# sequencer_final_version.net
KiCad netlist of a schematic drawn in Altium Designer
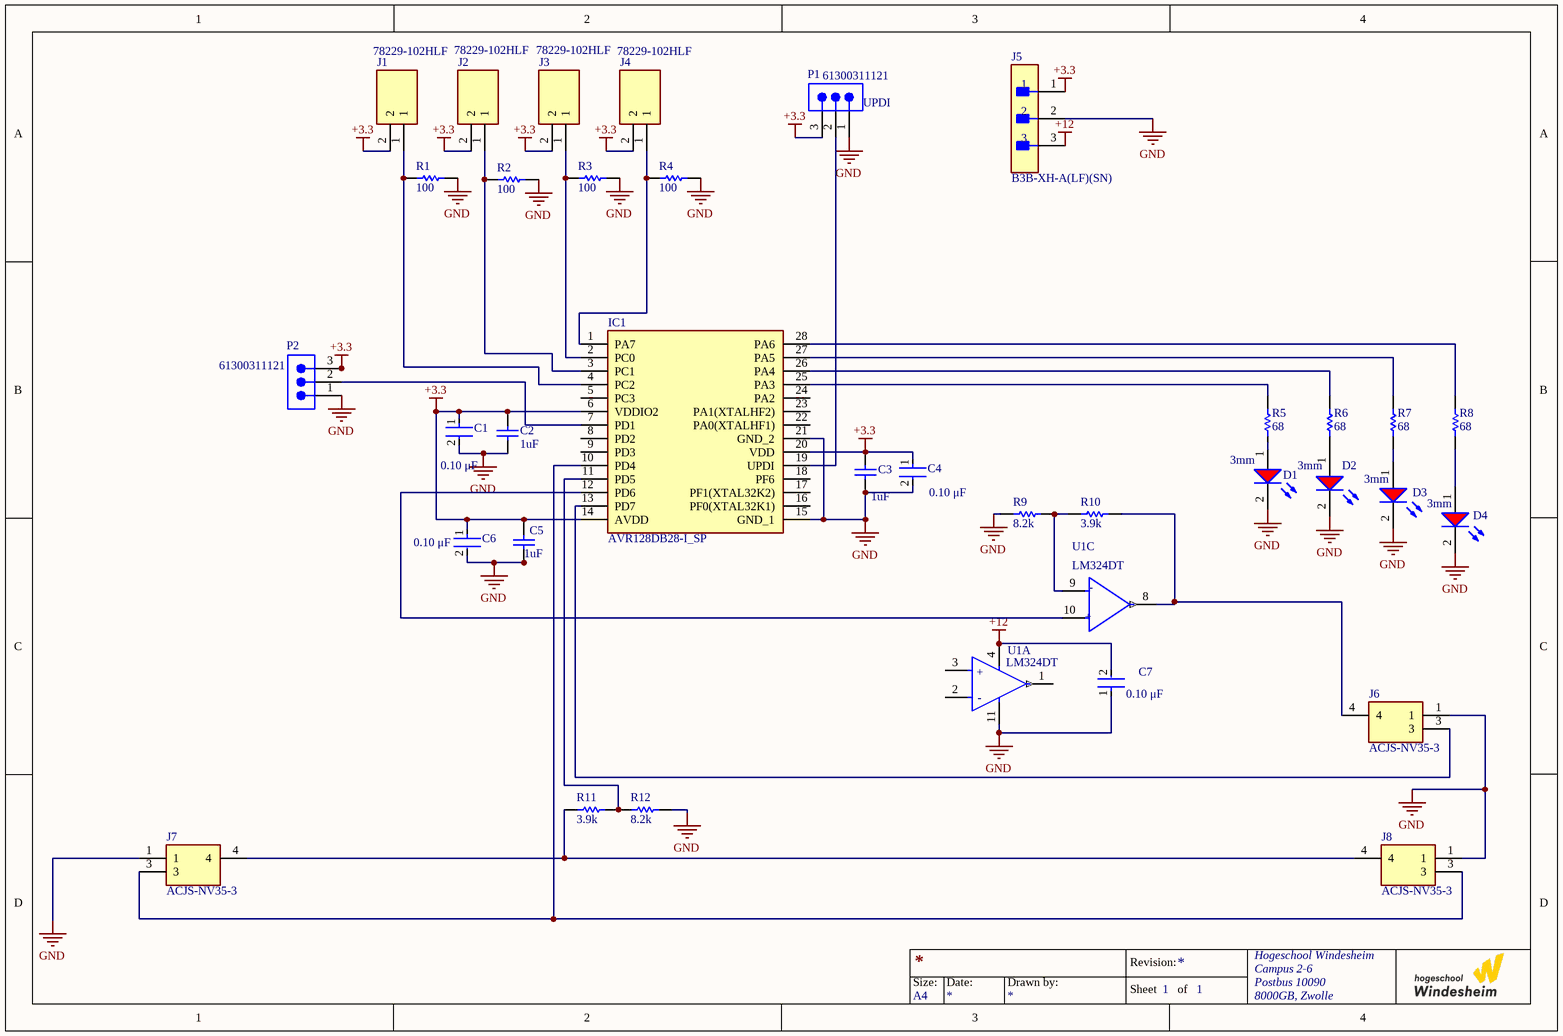
[diagram p0: sequencer final version.SchDoc]

(export (version "E")
  (design (tool "Eeschema 10.0.6"))
  (components
    (comp (ref "C1")
      (value "C1206C104K2RACTU")
      (footprint "FP-C1206C-EB-MFG")
      (description "CAP CER 0.1UF 200V 10% X7R 1206")
      (fields
        (field (name "TOLERANCE") "0.1")
        (field (name "OCTOPART") "https://octopart.com/c1206c104k2ractu-kemet-9138344")
        (field (name "CAPACITANCE") "0.10 μF")
      )
      (libsource (lib "Altium Content Vault") (part "b4654b650e69147ec39a6b967a45e02"))
    )
    (comp (ref "C2")
      (value "C1206C105K5RACTU")
      (footprint "CAPC3216X110X50LL20T25")
      (description "Chip Capacitor, 1 uF, +/- 10%, 50 V, -55 to 125 degC, 1206 (3216 Metric), RoHS, Tape and Reel")
      (fields
        (field (name "CAPACITANCE") "1uF")
        (field (name "MANUFACTURER") "Kemet")
        (field (name "TOLERANCE") "10%")
      )
      (libsource (lib "Altium Content Vault") (part "CAP-NP-2"))
    )
    (comp (ref "C3")
      (value "C1206C105K5RACTU")
      (footprint "CAPC3216X110X50LL20T25")
      (description "Chip Capacitor, 1 uF, +/- 10%, 50 V, -55 to 125 degC, 1206 (3216 Metric), RoHS, Tape and Reel")
      (fields
        (field (name "CAPACITANCE") "1uF")
        (field (name "MANUFACTURER") "Kemet")
        (field (name "TOLERANCE") "10%")
      )
      (libsource (lib "Altium Content Vault") (part "CAP-NP-2"))
    )
    (comp (ref "C4")
      (value "0.10 μF")
      (footprint "FP-C1206C-EB-MFG")
      (description "CAP CER 0.1UF 200V 10% X7R 1206")
      (fields (field (name "TOLERANCE") "0.1") (field (name "MANUFACTURER PART NUMBER") "C1206C104K2RACTU"))
      (libsource (lib "Altium Content Vault") (part "b4654b650e69147ec39a6b967a45e02"))
    )
    (comp (ref "C5")
      (value "C1206C105K5RACTU")
      (footprint "CAPC3216X110X50LL20T25")
      (description "Chip Capacitor, 1 uF, +/- 10%, 50 V, -55 to 125 degC, 1206 (3216 Metric), RoHS, Tape and Reel")
      (fields
        (field (name "CAPACITANCE") "1uF")
        (field (name "MANUFACTURER") "Kemet")
        (field (name "TOLERANCE") "10%")
      )
      (libsource (lib "Altium Content Vault") (part "CAP-NP-2"))
    )
    (comp (ref "C6")
      (value "0.10 μF")
      (footprint "FP-C1206C-EB-MFG")
      (description "CAP CER 0.1UF 200V 10% X7R 1206")
      (fields (field (name "TOLERANCE") "0.1") (field (name "MANUFACTURER PART NUMBER") "C1206C104K2RACTU"))
      (libsource (lib "Altium Content Vault") (part "b4654b650e69147ec39a6b967a45e02"))
    )
    (comp (ref "C7")
      (value "0.10 μF")
      (footprint "FP-C1206C-EB-MFG")
      (description "CAP CER 0.1UF 200V 10% X7R 1206")
      (fields (field (name "TOLERANCE") "0.1") (field (name "MANUFACTURER PART NUMBER") "C1206C104K2RACTU"))
      (libsource (lib "Altium Content Vault") (part "b4654b650e69147ec39a6b967a45e02"))
    )
    (comp (ref "D1")
      (value "151031SS04000")
      (footprint "WL-TMRC_D3.95H5.3")
      (fields (field (name "LENS SIZE") "3mm"))
      (libsource (lib "Altium Content Vault") (part "LED_Red_1A-2K"))
    )
    (comp (ref "D2")
      (value "151031SS04000")
      (footprint "WL-TMRC_D3.95H5.3")
      (fields (field (name "LENS SIZE") "3mm"))
      (libsource (lib "Altium Content Vault") (part "LED_Red_1A-2K"))
    )
    (comp (ref "D3")
      (value "151031SS04000")
      (footprint "WL-TMRC_D3.95H5.3")
      (fields (field (name "LENS SIZE") "3mm"))
      (libsource (lib "Altium Content Vault") (part "LED_Red_1A-2K"))
    )
    (comp (ref "D4")
      (value "151031SS04000")
      (footprint "WL-TMRC_D3.95H5.3")
      (fields (field (name "LENS SIZE") "3mm"))
      (libsource (lib "Altium Content Vault") (part "LED_Red_1A-2K"))
    )
    (comp (ref "IC1")
      (value "AVR128DB28-I_SP")
      (footprint "SamacSys:DIP794W56P254L3486H508Q28N")
      (description "Integrated Circuit")
      (fields
        (field (name "MANUFACTURER_PART_NUMBER") "AVR128DB28-I/SP")
        (field (name "MOUSER PART NUMBER") "579-AVR128DB28-I/SP")
      )
      (libsource (lib "*") (part "AVR128DB28-I_SP"))
    )
    (comp (ref "J1")
      (value "78229-102HLF")
      (footprint "SamacSys:HDRV2W67P0X254_1X2_508X241X1082P")
      (description "Connector")
      (libsource (lib "*") (part "78229-102HLF"))
    )
    (comp (ref "J2")
      (value "78229-102HLF")
      (footprint "SamacSys:HDRV2W67P0X254_1X2_508X241X1082P")
      (description "Connector")
      (libsource (lib "*") (part "78229-102HLF"))
    )
    (comp (ref "J3")
      (value "78229-102HLF")
      (footprint "SamacSys:HDRV2W67P0X254_1X2_508X241X1082P")
      (description "Connector")
      (libsource (lib "*") (part "78229-102HLF"))
    )
    (comp (ref "J4")
      (value "78229-102HLF")
      (footprint "SamacSys:HDRV2W67P0X254_1X2_508X241X1082P")
      (description "Connector")
      (libsource (lib "*") (part "78229-102HLF"))
    )
    (comp (ref "J5")
      (value "B3B-XH-A(LF)(SN)")
      (footprint "FP-B3B-XH-A_LF_SN-MFG")
      (description "CONN HEADER VERT 3POS 2.5MM")
      (libsource (lib "Altium Content Vault") (part "0d3f023dd272f625e17a2be33dea85f"))
    )
    (comp (ref "J6")
      (value "ACJS-NV35-3")
      (footprint "SamacSys:ACJSNV353")
      (description "Connector")
      (fields (field (name "MOUSER PART NUMBER") "523-ACJS-NV35-3"))
      (libsource (lib "*") (part "ACJS-NV35-3"))
    )
    (comp (ref "J7")
      (value "ACJS-NV35-3")
      (footprint "SamacSys:ACJSNV353")
      (description "Connector")
      (fields (field (name "MOUSER PART NUMBER") "523-ACJS-NV35-3"))
      (libsource (lib "") (part "ACJS-NV35-3_1"))
    )
    (comp (ref "J8")
      (value "ACJS-NV35-3")
      (footprint "SamacSys:ACJSNV353")
      (description "Connector")
      (fields (field (name "MOUSER PART NUMBER") "523-ACJS-NV35-3"))
      (libsource (lib "*") (part "ACJS-NV35-3"))
    )
    (comp (ref "P1")
      (value "61300311121")
      (footprint "61300311121")
      (description "Potmeter connectie")
      (libsource (lib "Altium Content Vault") (part "Header_Male_1R_03P"))
    )
    (comp (ref "P2")
      (value "61300311121")
      (footprint "61300311121")
      (description "Potmeter connectie")
      (libsource (lib "Altium Content Vault") (part "Header_Male_1R_03P"))
    )
    (comp (ref "R1")
      (value "100")
      (footprint "RESC3216X70X50NL05T20")
      (fields (field (name "MANUFACTURER") "Panasonic") (field (name "PART NUMBER") "ERJ-8ENF1000V"))
      (libsource (lib "Altium Content Vault") (part "RES"))
    )
    (comp (ref "R2")
      (value "100")
      (footprint "RESC3216X70X50NL05T20")
      (fields (field (name "MANUFACTURER") "Panasonic") (field (name "PART NUMBER") "ERJ-8ENF1000V"))
      (libsource (lib "Altium Content Vault") (part "RES"))
    )
    (comp (ref "R3")
      (value "100")
      (footprint "RESC3216X70X50NL05T20")
      (fields (field (name "MANUFACTURER") "Panasonic") (field (name "PART NUMBER") "ERJ-8ENF1000V"))
      (libsource (lib "Altium Content Vault") (part "RES"))
    )
    (comp (ref "R4")
      (value "100")
      (footprint "RESC3216X70X50NL05T20")
      (fields (field (name "MANUFACTURER") "Panasonic") (field (name "PART NUMBER") "ERJ-8ENF1000V"))
      (libsource (lib "Altium Content Vault") (part "RES"))
    )
    (comp (ref "R5")
      (value "68")
      (footprint "RESC3216X60X45LL10T20")
      (fields (field (name "MANUFACTURER") "Vishay Dale") (field (name "PART NUMBER") "CRCW120668R0FKEA"))
      (libsource (lib "Altium Content Vault") (part "RES"))
    )
    (comp (ref "R6")
      (value "68")
      (footprint "RESC3216X60X45LL10T20")
      (fields (field (name "MANUFACTURER") "Vishay Dale") (field (name "PART NUMBER") "CRCW120668R0FKEA"))
      (libsource (lib "Altium Content Vault") (part "RES"))
    )
    (comp (ref "R7")
      (value "68")
      (footprint "RESC3216X60X45LL10T20")
      (fields (field (name "MANUFACTURER") "Vishay Dale") (field (name "PART NUMBER") "CRCW120668R0FKEA"))
      (libsource (lib "Altium Content Vault") (part "RES"))
    )
    (comp (ref "R8")
      (value "68")
      (footprint "RESC3216X60X45LL10T20")
      (fields (field (name "MANUFACTURER") "Vishay Dale") (field (name "PART NUMBER") "CRCW120668R0FKEA"))
      (libsource (lib "Altium Content Vault") (part "RES"))
    )
    (comp (ref "R9")
      (value "8.2k")
      (footprint "RESC3216X60X45NL10T20")
      (fields (field (name "MANUFACTURER") "Vishay Dale") (field (name "PART NUMBER") "CRCW12063K90FKEA"))
      (libsource (lib "Altium Content Vault") (part "RES"))
    )
    (comp (ref "R10")
      (value "3.9k")
      (footprint "RESC3216X70X50ML20T25")
      (fields (field (name "PART NUMBER") "ERA8AEB202V") (field (name "MANUFACTURER") "Panasonic"))
      (libsource (lib "Altium Content Vault") (part "RES"))
    )
    (comp (ref "R11")
      (value "3.9k")
      (footprint "RESC3216X70X50ML20T25")
      (fields (field (name "PART NUMBER") "ERA8AEB202V") (field (name "MANUFACTURER") "Panasonic"))
      (libsource (lib "Altium Content Vault") (part "RES"))
    )
    (comp (ref "R12")
      (value "8.2k")
      (footprint "RESC3216X60X45NL10T20")
      (fields (field (name "MANUFACTURER") "Vishay Dale") (field (name "PART NUMBER") "CRCW12063K90FKEA"))
      (libsource (lib "Altium Content Vault") (part "RES"))
    )
    (comp (ref "U1")
      (value "LM324DT")
      (footprint "FP-SO-14-MFG")
      (description "IC OPAMP GP 4 CIRCUIT 14SO")
      (fields
        (field (name "OCTOPART") "https://octopart.com/lm324dt-stmicroelectronics-39579146")
        (field (name "MANUFACTURER") "STMicroelectronics")
      )
      (libsource (lib "Altium Content Vault") (part "a065ef67e5aa9ef3942d43d6008d043"))
    )
  )
  (nets
    (net (code "1") (name "+3.3") (class "Default")
      (node (ref "C1") (pin "1") (pinfunction "1_1") (pintype "passive"))
      (node (ref "C2") (pin "2") (pinfunction "2_2") (pintype "passive"))
      (node (ref "C3") (pin "2") (pinfunction "2_2") (pintype "passive"))
      (node (ref "C4") (pin "1") (pinfunction "1_1") (pintype "passive"))
      (node (ref "C5") (pin "2") (pinfunction "2_2") (pintype "passive"))
      (node (ref "C6") (pin "1") (pinfunction "1_1") (pintype "passive"))
      (node (ref "IC1") (pin "14") (pinfunction "AVDD_14") (pintype "passive"))
      (node (ref "IC1") (pin "20") (pinfunction "VDD_20") (pintype "passive"))
      (node (ref "IC1") (pin "6") (pinfunction "VDDIO2_6") (pintype "passive"))
      (node (ref "J1") (pin "2") (pinfunction "2_2") (pintype "passive"))
      (node (ref "J2") (pin "2") (pinfunction "2_2") (pintype "passive"))
      (node (ref "J3") (pin "2") (pinfunction "2_2") (pintype "passive"))
      (node (ref "J4") (pin "2") (pinfunction "2_2") (pintype "passive"))
      (node (ref "J5") (pin "1") (pinfunction "1_1") (pintype "passive"))
      (node (ref "P1") (pin "3") (pinfunction "3_3") (pintype "passive"))
      (node (ref "P2") (pin "3") (pinfunction "3_3") (pintype "passive"))
    )
    (net (code "2") (name "+12") (class "Default")
      (node (ref "C7") (pin "2") (pinfunction "2_2") (pintype "passive"))
      (node (ref "J5") (pin "3") (pinfunction "3_3") (pintype "passive"))
      (node (ref "U1") (pin "4") (pinfunction "VCC+_4") (pintype "power_in"))
    )
    (net (code "3") (name "GND") (class "Default")
      (node (ref "C1") (pin "2") (pinfunction "2_2") (pintype "passive"))
      (node (ref "C2") (pin "1") (pinfunction "1_1") (pintype "passive"))
      (node (ref "C3") (pin "1") (pinfunction "1_1") (pintype "passive"))
      (node (ref "C4") (pin "2") (pinfunction "2_2") (pintype "passive"))
      (node (ref "C5") (pin "1") (pinfunction "1_1") (pintype "passive"))
      (node (ref "C6") (pin "2") (pinfunction "2_2") (pintype "passive"))
      (node (ref "C7") (pin "1") (pinfunction "1_1") (pintype "passive"))
      (node (ref "D1") (pin "2") (pinfunction "K_2") (pintype "passive"))
      (node (ref "D2") (pin "2") (pinfunction "K_2") (pintype "passive"))
      (node (ref "D3") (pin "2") (pinfunction "K_2") (pintype "passive"))
      (node (ref "D4") (pin "2") (pinfunction "K_2") (pintype "passive"))
      (node (ref "IC1") (pin "15") (pinfunction "GND_1_15") (pintype "passive"))
      (node (ref "IC1") (pin "21") (pinfunction "GND_2_21") (pintype "passive"))
      (node (ref "J5") (pin "2") (pinfunction "2_2") (pintype "passive"))
      (node (ref "J6") (pin "1") (pinfunction "1_1") (pintype "passive"))
      (node (ref "J7") (pin "1") (pinfunction "1_1") (pintype "passive"))
      (node (ref "J8") (pin "1") (pinfunction "1_1") (pintype "passive"))
      (node (ref "P1") (pin "1") (pinfunction "1_1") (pintype "passive"))
      (node (ref "P2") (pin "1") (pinfunction "1_1") (pintype "passive"))
      (node (ref "R1") (pin "2") (pinfunction "2_2") (pintype "passive"))
      (node (ref "R12") (pin "2") (pinfunction "2_2") (pintype "passive"))
      (node (ref "R2") (pin "2") (pinfunction "2_2") (pintype "passive"))
      (node (ref "R3") (pin "2") (pinfunction "2_2") (pintype "passive"))
      (node (ref "R4") (pin "2") (pinfunction "2_2") (pintype "passive"))
      (node (ref "R9") (pin "1") (pinfunction "1_1") (pintype "passive"))
      (node (ref "U1") (pin "11") (pinfunction "VCC-_11") (pintype "power_in"))
    )
    (net (code "4") (name "Net-(D1-A)") (class "Default")
      (node (ref "D1") (pin "1") (pinfunction "A_1") (pintype "passive"))
      (node (ref "R5") (pin "1") (pinfunction "1_1") (pintype "passive"))
    )
    (net (code "5") (name "Net-(D2-A)") (class "Default")
      (node (ref "D2") (pin "1") (pinfunction "A_1") (pintype "passive"))
      (node (ref "R6") (pin "1") (pinfunction "1_1") (pintype "passive"))
    )
    (net (code "6") (name "Net-(D3-A)") (class "Default")
      (node (ref "D3") (pin "1") (pinfunction "A_1") (pintype "passive"))
      (node (ref "R7") (pin "1") (pinfunction "1_1") (pintype "passive"))
    )
    (net (code "7") (name "Net-(D4-A)") (class "Default")
      (node (ref "D4") (pin "1") (pinfunction "A_1") (pintype "passive"))
      (node (ref "R8") (pin "1") (pinfunction "1_1") (pintype "passive"))
    )
    (net (code "8") (name "Net-(IC1-PA3)") (class "Default")
      (node (ref "IC1") (pin "25") (pinfunction "PA3_25") (pintype "passive"))
      (node (ref "R5") (pin "2") (pinfunction "2_2") (pintype "passive"))
    )
    (net (code "9") (name "Net-(IC1-PA4)") (class "Default")
      (node (ref "IC1") (pin "26") (pinfunction "PA4_26") (pintype "passive"))
      (node (ref "R6") (pin "2") (pinfunction "2_2") (pintype "passive"))
    )
    (net (code "10") (name "Net-(IC1-PA5)") (class "Default")
      (node (ref "IC1") (pin "27") (pinfunction "PA5_27") (pintype "passive"))
      (node (ref "R7") (pin "2") (pinfunction "2_2") (pintype "passive"))
    )
    (net (code "11") (name "Net-(IC1-PA6)") (class "Default")
      (node (ref "IC1") (pin "28") (pinfunction "PA6_28") (pintype "passive"))
      (node (ref "R8") (pin "2") (pinfunction "2_2") (pintype "passive"))
    )
    (net (code "12") (name "Net-(IC1-PA7)") (class "Default")
      (node (ref "IC1") (pin "1") (pinfunction "PA7_1") (pintype "passive"))
      (node (ref "J4") (pin "1") (pinfunction "1_1") (pintype "passive"))
      (node (ref "R4") (pin "1") (pinfunction "1_1") (pintype "passive"))
    )
    (net (code "13") (name "Net-(IC1-PC0)") (class "Default")
      (node (ref "IC1") (pin "2") (pinfunction "PC0_2") (pintype "passive"))
      (node (ref "J3") (pin "1") (pinfunction "1_1") (pintype "passive"))
      (node (ref "R3") (pin "1") (pinfunction "1_1") (pintype "passive"))
    )
    (net (code "14") (name "Net-(IC1-PC1)") (class "Default")
      (node (ref "IC1") (pin "3") (pinfunction "PC1_3") (pintype "passive"))
      (node (ref "J2") (pin "1") (pinfunction "1_1") (pintype "passive"))
      (node (ref "R2") (pin "1") (pinfunction "1_1") (pintype "passive"))
    )
    (net (code "15") (name "Net-(IC1-PC2)") (class "Default")
      (node (ref "IC1") (pin "4") (pinfunction "PC2_4") (pintype "passive"))
      (node (ref "J1") (pin "1") (pinfunction "1_1") (pintype "passive"))
      (node (ref "R1") (pin "1") (pinfunction "1_1") (pintype "passive"))
    )
    (net (code "16") (name "Net-(IC1-PD1)") (class "Default")
      (node (ref "IC1") (pin "7") (pinfunction "PD1_7") (pintype "passive"))
      (node (ref "P2") (pin "2") (pinfunction "2_2") (pintype "passive"))
    )
    (net (code "17") (name "Net-(IC1-PD4)") (class "Default")
      (node (ref "IC1") (pin "10") (pinfunction "PD4_10") (pintype "passive"))
      (node (ref "J7") (pin "3") (pinfunction "3_3") (pintype "passive"))
      (node (ref "J8") (pin "3") (pinfunction "3_3") (pintype "passive"))
    )
    (net (code "18") (name "Net-(IC1-PD5)") (class "Default")
      (node (ref "IC1") (pin "11") (pinfunction "PD5_11") (pintype "passive"))
      (node (ref "R11") (pin "2") (pinfunction "2_2") (pintype "passive"))
      (node (ref "R12") (pin "1") (pinfunction "1_1") (pintype "passive"))
    )
    (net (code "19") (name "Net-(IC1-PD6)") (class "Default")
      (node (ref "IC1") (pin "12") (pinfunction "PD6_12") (pintype "passive"))
      (node (ref "U1") (pin "10") (pinfunction "Non-Inverting_Input_3_10") (pintype "tri_state"))
    )
    (net (code "20") (name "Net-(IC1-PD7)") (class "Default")
      (node (ref "IC1") (pin "13") (pinfunction "PD7_13") (pintype "passive"))
      (node (ref "J6") (pin "3") (pinfunction "3_3") (pintype "passive"))
    )
    (net (code "21") (name "Net-(IC1-UPDI)") (class "Default")
      (node (ref "IC1") (pin "19") (pinfunction "UPDI_19") (pintype "passive"))
      (node (ref "P1") (pin "2") (pinfunction "2_2") (pintype "passive"))
    )
    (net (code "22") (name "Net-(J7-Pad4)") (class "Default")
      (node (ref "J7") (pin "4") (pinfunction "4_4") (pintype "passive"))
      (node (ref "J8") (pin "4") (pinfunction "4_4") (pintype "passive"))
      (node (ref "R11") (pin "1") (pinfunction "1_1") (pintype "passive"))
    )
    (net (code "23") (name "Net-(U1C-Inverting_Input_3)") (class "Default")
      (node (ref "R10") (pin "1") (pinfunction "1_1") (pintype "passive"))
      (node (ref "R9") (pin "2") (pinfunction "2_2") (pintype "passive"))
      (node (ref "U1") (pin "9") (pinfunction "Inverting_Input_3_9") (pintype "tri_state"))
    )
    (net (code "24") (name "Net-(U1C-Output_3)") (class "Default")
      (node (ref "J6") (pin "4") (pinfunction "4_4") (pintype "passive"))
      (node (ref "R10") (pin "2") (pinfunction "2_2") (pintype "passive"))
      (node (ref "U1") (pin "8") (pinfunction "Output_3_8") (pintype "output"))
    )
    (net (code "25") (name "unconnected-(IC1-PA0(XTALHF1)-Pad22)") (class "Default")
      (node (ref "IC1") (pin "22") (pinfunction "PA0(XTALHF1)_22") (pintype "passive"))
    )
    (net (code "26") (name "unconnected-(IC1-PA1(XTALHF2)-Pad23)") (class "Default")
      (node (ref "IC1") (pin "23") (pinfunction "PA1(XTALHF2)_23") (pintype "passive"))
    )
    (net (code "27") (name "unconnected-(IC1-PA2-Pad24)") (class "Default")
      (node (ref "IC1") (pin "24") (pinfunction "PA2_24") (pintype "passive"))
    )
    (net (code "28") (name "unconnected-(IC1-PC3-Pad5)") (class "Default")
      (node (ref "IC1") (pin "5") (pinfunction "PC3_5") (pintype "passive"))
    )
    (net (code "29") (name "unconnected-(IC1-PD2-Pad8)") (class "Default")
      (node (ref "IC1") (pin "8") (pinfunction "PD2_8") (pintype "passive"))
    )
    (net (code "30") (name "unconnected-(IC1-PD3-Pad9)") (class "Default")
      (node (ref "IC1") (pin "9") (pinfunction "PD3_9") (pintype "passive"))
    )
    (net (code "31") (name "unconnected-(IC1-PF0(XTAL32K1)-Pad16)") (class "Default")
      (node (ref "IC1") (pin "16") (pinfunction "PF0(XTAL32K1)_16") (pintype "passive"))
    )
    (net (code "32") (name "unconnected-(IC1-PF1(XTAL32K2)-Pad17)") (class "Default")
      (node (ref "IC1") (pin "17") (pinfunction "PF1(XTAL32K2)_17") (pintype "passive"))
    )
    (net (code "33") (name "unconnected-(IC1-PF6-Pad18)") (class "Default")
      (node (ref "IC1") (pin "18") (pinfunction "PF6_18") (pintype "passive"))
    )
    (net (code "34") (name "unconnected-(U1A-Inverting_Input_1-Pad2)") (class "Default")
      (node (ref "U1") (pin "2") (pinfunction "Inverting_Input_1_2") (pintype "tri_state"))
    )
    (net (code "35") (name "unconnected-(U1A-Non-Inverting_Input_1-Pad3)") (class "Default")
      (node (ref "U1") (pin "3") (pinfunction "Non-Inverting_Input_1_3") (pintype "tri_state"))
    )
    (net (code "36") (name "unconnected-(U1A-Output_1-Pad1)") (class "Default")
      (node (ref "U1") (pin "1") (pinfunction "Output_1_1") (pintype "output"))
    )
  )
)
